# ControlModule-pan.net
KiCad netlist of a schematic drawn in EAGLE
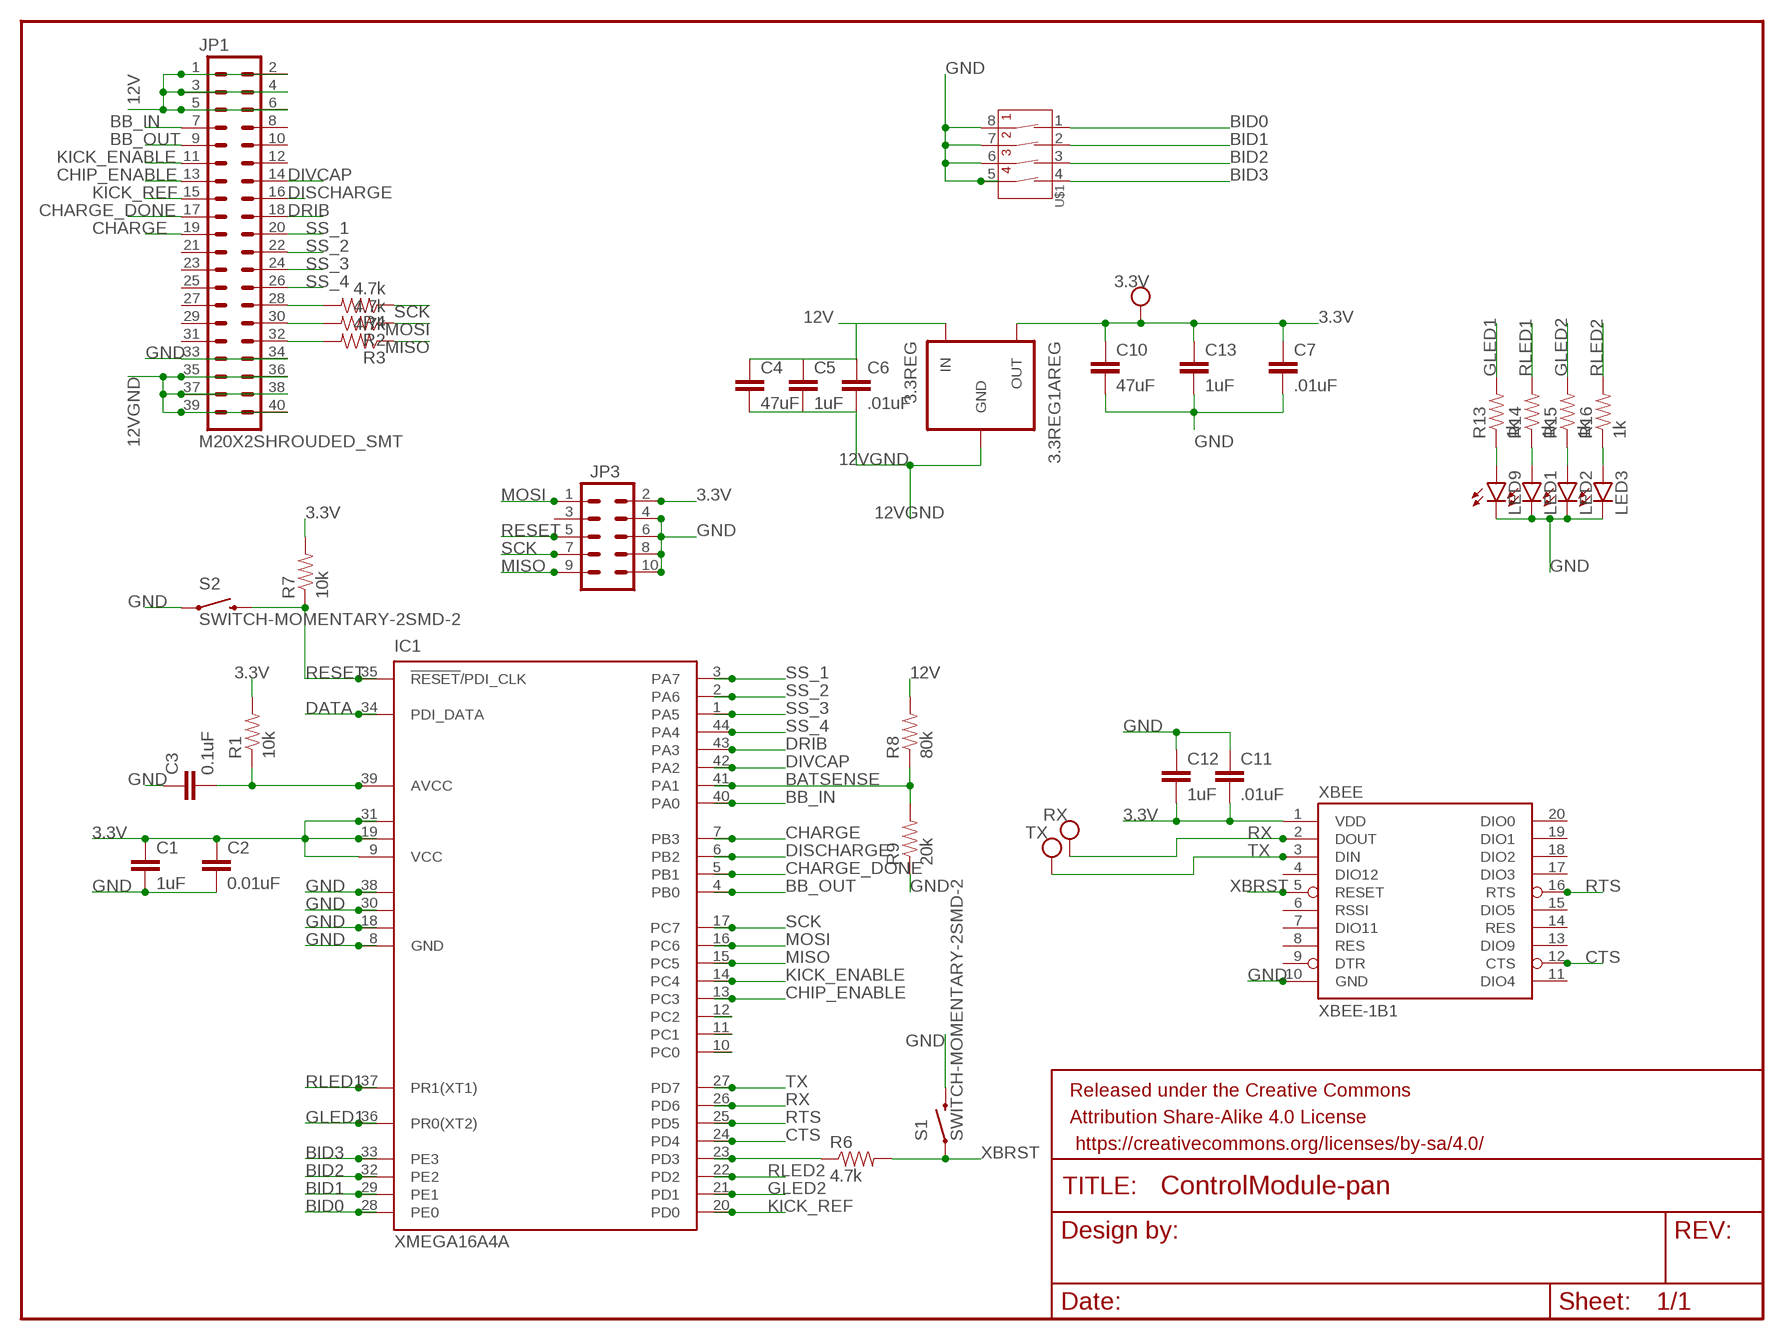
[diagram p0: schematic, sheet 1]

(export (version "E")
  (design (tool "Eeschema 10.0.6"))
  (components
    (comp (ref "3.3REG")
      (value "3.3REG1AREG")
      (footprint "eagle-import:DPAK")
      (libsource (lib "eagle-import") (part "3.3REG1AREG"))
    )
    (comp (ref "3.3V")
      (value "TEST_PT")
      (footprint "eagle-import:TESTING_PT")
      (libsource (lib "eagle-import") (part "TEST_PT"))
    )
    (comp (ref "C1")
      (value "1uF")
      (footprint "eagle-import:0805")
      (libsource (lib "eagle-import") (part "CAP0805"))
    )
    (comp (ref "C2")
      (value "0.01uF")
      (footprint "eagle-import:0805")
      (libsource (lib "eagle-import") (part "CAP0805"))
    )
    (comp (ref "C3")
      (value "0.1uF")
      (footprint "eagle-import:0805")
      (libsource (lib "eagle-import") (part "CAP0805"))
    )
    (comp (ref "C4")
      (value "47uF")
      (footprint "eagle-import:1206")
      (libsource (lib "eagle-import") (part "CAP1206"))
    )
    (comp (ref "C5")
      (value "1uF")
      (footprint "eagle-import:0805")
      (libsource (lib "eagle-import") (part "CAP0805"))
    )
    (comp (ref "C6")
      (value ".01uF")
      (footprint "eagle-import:0805")
      (libsource (lib "eagle-import") (part "CAP0805"))
    )
    (comp (ref "C7")
      (value ".01uF")
      (footprint "eagle-import:0805")
      (libsource (lib "eagle-import") (part "CAP0805"))
    )
    (comp (ref "C10")
      (value "47uF")
      (footprint "eagle-import:1206")
      (libsource (lib "eagle-import") (part "CAP1206"))
    )
    (comp (ref "C11")
      (value ".01uF")
      (footprint "eagle-import:0805")
      (libsource (lib "eagle-import") (part "CAP0805"))
    )
    (comp (ref "C12")
      (value "1uF")
      (footprint "eagle-import:0805")
      (libsource (lib "eagle-import") (part "CAP0805"))
    )
    (comp (ref "C13")
      (value "1uF")
      (footprint "eagle-import:0805")
      (libsource (lib "eagle-import") (part "CAP0805"))
    )
    (comp (ref "FRAME1")
      (value "FRAME-LETTER")
      (footprint "eagle-import:CREATIVE_COMMONS")
      (libsource (lib "eagle-import") (part "FRAME-LETTER"))
    )
    (comp (ref "IC1")
      (value "XMEGA16A4A")
      (footprint "eagle-import:TQFP44")
      (libsource (lib "eagle-import") (part "XMEGA16A4A"))
    )
    (comp (ref "JP1")
      (value "M20X2SHROUDED_SMT")
      (footprint "eagle-import:2X20_SHROUDED_SMT")
      (libsource (lib "eagle-import") (part "M20X2SHROUDED_SMT"))
    )
    (comp (ref "JP3")
      (value "M05X2SHD")
      (footprint "eagle-import:2X5-SHROUDED")
      (libsource (lib "eagle-import") (part "M05X2SHD"))
    )
    (comp (ref "LED1")
      (value "LED1206")
      (footprint "eagle-import:LED-1206")
      (libsource (lib "eagle-import") (part "LED1206"))
    )
    (comp (ref "LED2")
      (value "LED1206")
      (footprint "eagle-import:LED-1206")
      (libsource (lib "eagle-import") (part "LED1206"))
    )
    (comp (ref "LED3")
      (value "LED1206")
      (footprint "eagle-import:LED-1206")
      (libsource (lib "eagle-import") (part "LED1206"))
    )
    (comp (ref "LED9")
      (value "LED1206")
      (footprint "eagle-import:LED-1206")
      (libsource (lib "eagle-import") (part "LED1206"))
    )
    (comp (ref "R1")
      (value "10k")
      (footprint "eagle-import:0805")
      (libsource (lib "eagle-import") (part "RESISTOR0805-RES"))
    )
    (comp (ref "R2")
      (value "4.7k")
      (footprint "eagle-import:0805")
      (libsource (lib "eagle-import") (part "SparkFun-Resistors_RESISTOR0805-RES"))
    )
    (comp (ref "R3")
      (value "4.7k")
      (footprint "eagle-import:0805")
      (libsource (lib "eagle-import") (part "SparkFun-Resistors_RESISTOR0805-RES"))
    )
    (comp (ref "R4")
      (value "4.7k")
      (footprint "eagle-import:0805")
      (libsource (lib "eagle-import") (part "SparkFun-Resistors_RESISTOR0805-RES"))
    )
    (comp (ref "R6")
      (value "4.7k")
      (footprint "eagle-import:0805")
      (libsource (lib "eagle-import") (part "RESISTOR0805-RES"))
    )
    (comp (ref "R7")
      (value "10k")
      (footprint "eagle-import:0805")
      (libsource (lib "eagle-import") (part "RESISTOR0805-RES"))
    )
    (comp (ref "R8")
      (value "80k")
      (footprint "eagle-import:0805")
      (libsource (lib "eagle-import") (part "RESISTOR0805-RES"))
    )
    (comp (ref "R9")
      (value "20k")
      (footprint "eagle-import:0805")
      (libsource (lib "eagle-import") (part "RESISTOR0805-RES"))
    )
    (comp (ref "R13")
      (value "1k")
      (footprint "eagle-import:0805")
      (libsource (lib "eagle-import") (part "RESISTOR0805-RES"))
    )
    (comp (ref "R14")
      (value "1k")
      (footprint "eagle-import:0805")
      (libsource (lib "eagle-import") (part "RESISTOR0805-RES"))
    )
    (comp (ref "R15")
      (value "1k")
      (footprint "eagle-import:0805")
      (libsource (lib "eagle-import") (part "RESISTOR0805-RES"))
    )
    (comp (ref "R16")
      (value "1k")
      (footprint "eagle-import:0805")
      (libsource (lib "eagle-import") (part "RESISTOR0805-RES"))
    )
    (comp (ref "RX")
      (value "TEST_PT")
      (footprint "eagle-import:TESTING_PT")
      (libsource (lib "eagle-import") (part "TEST_PT"))
    )
    (comp (ref "S1")
      (value "SWITCH-MOMENTARY-2SMD-2")
      (footprint "eagle-import:TACTILE_SWITCH_SMD-2")
      (libsource (lib "eagle-import") (part "SWITCH-MOMENTARY-2SMD-2"))
    )
    (comp (ref "S2")
      (value "SWITCH-MOMENTARY-2SMD-2")
      (footprint "eagle-import:TACTILE_SWITCH_SMD-2")
      (libsource (lib "eagle-import") (part "SWITCH-MOMENTARY-2SMD-2"))
    )
    (comp (ref "TX")
      (value "TEST_PT")
      (footprint "eagle-import:TESTING_PT")
      (libsource (lib "eagle-import") (part "TEST_PT"))
    )
    (comp (ref "U$1")
      (value "4-POS-DIP")
      (footprint "eagle-import:4-POS-DIP-SMD")
      (libsource (lib "eagle-import") (part "4-POS-DIP"))
    )
    (comp (ref "XBEE")
      (value "XBEE-1B1")
      (footprint "eagle-import:XBEE-1")
      (libsource (lib "eagle-import") (part "XBEE-1B1"))
    )
  )
  (nets
    (net (code "1") (name "/3.3V") (class "Default")
      (node (ref "3.3REG") (pin "SOURCE") (pinfunction "OUT_SOURCE") (pintype "bidirectional"))
      (node (ref "3.3V") (pin "P$1") (pinfunction "P$1_P$1") (pintype "bidirectional"))
      (node (ref "C1") (pin "1") (pinfunction "1_1") (pintype "passive"))
      (node (ref "C10") (pin "1") (pinfunction "1_1") (pintype "passive"))
      (node (ref "C11") (pin "2") (pinfunction "2_2") (pintype "passive"))
      (node (ref "C12") (pin "2") (pinfunction "2_2") (pintype "passive"))
      (node (ref "C13") (pin "1") (pinfunction "1_1") (pintype "passive"))
      (node (ref "C2") (pin "1") (pinfunction "1_1") (pintype "passive"))
      (node (ref "C7") (pin "1") (pinfunction "1_1") (pintype "passive"))
      (node (ref "IC1") (pin "19") (pinfunction "VCC1_19") (pintype "power_in"))
      (node (ref "IC1") (pin "31") (pinfunction "VCC2_31") (pintype "power_in"))
      (node (ref "IC1") (pin "9") (pinfunction "VCC_9") (pintype "power_in"))
      (node (ref "JP3") (pin "2") (pinfunction "2_2") (pintype "passive"))
      (node (ref "R1") (pin "2") (pinfunction "2_2") (pintype "passive"))
      (node (ref "R7") (pin "2") (pinfunction "2_2") (pintype "passive"))
      (node (ref "XBEE") (pin "1") (pinfunction "VDD_1") (pintype "power_in"))
    )
    (net (code "2") (name "/12V") (class "Default")
      (node (ref "3.3REG") (pin "GATE") (pinfunction "IN_GATE") (pintype "input"))
      (node (ref "C4") (pin "1") (pinfunction "1_1") (pintype "passive"))
      (node (ref "C5") (pin "1") (pinfunction "1_1") (pintype "passive"))
      (node (ref "C6") (pin "1") (pinfunction "1_1") (pintype "passive"))
      (node (ref "JP1") (pin "1") (pinfunction "1_1") (pintype "passive"))
      (node (ref "JP1") (pin "2") (pinfunction "2_2") (pintype "passive"))
      (node (ref "JP1") (pin "3") (pinfunction "3_3") (pintype "passive"))
      (node (ref "JP1") (pin "4") (pinfunction "4_4") (pintype "passive"))
      (node (ref "JP1") (pin "5") (pinfunction "5_5") (pintype "passive"))
      (node (ref "JP1") (pin "6") (pinfunction "6_6") (pintype "passive"))
      (node (ref "R8") (pin "2") (pinfunction "2_2") (pintype "passive"))
    )
    (net (code "3") (name "/12VGND") (class "Default")
      (node (ref "3.3REG") (pin "DRAIN") (pinfunction "GND_DRAIN") (pintype "bidirectional"))
      (node (ref "C4") (pin "2") (pinfunction "2_2") (pintype "passive"))
      (node (ref "C5") (pin "2") (pinfunction "2_2") (pintype "passive"))
      (node (ref "C6") (pin "2") (pinfunction "2_2") (pintype "passive"))
      (node (ref "JP1") (pin "35") (pinfunction "35_35") (pintype "passive"))
      (node (ref "JP1") (pin "36") (pinfunction "36_36") (pintype "passive"))
      (node (ref "JP1") (pin "37") (pinfunction "37_37") (pintype "passive"))
      (node (ref "JP1") (pin "38") (pinfunction "38_38") (pintype "passive"))
      (node (ref "JP1") (pin "39") (pinfunction "39_39") (pintype "passive"))
      (node (ref "JP1") (pin "40") (pinfunction "40_40") (pintype "passive"))
    )
    (net (code "4") (name "/BATSENSE") (class "Default")
      (node (ref "IC1") (pin "41") (pinfunction "PA1_41") (pintype "bidirectional"))
      (node (ref "R8") (pin "1") (pinfunction "1_1") (pintype "passive"))
      (node (ref "R9") (pin "2") (pinfunction "2_2") (pintype "passive"))
    )
    (net (code "5") (name "/BB_IN") (class "Default")
      (node (ref "IC1") (pin "40") (pinfunction "PA0_40") (pintype "bidirectional"))
      (node (ref "JP1") (pin "7") (pinfunction "7_7") (pintype "passive"))
    )
    (net (code "6") (name "/BB_OUT") (class "Default")
      (node (ref "IC1") (pin "4") (pinfunction "PB0_4") (pintype "bidirectional"))
      (node (ref "JP1") (pin "9") (pinfunction "9_9") (pintype "passive"))
    )
    (net (code "7") (name "/BID0") (class "Default")
      (node (ref "IC1") (pin "28") (pinfunction "PE0_28") (pintype "bidirectional"))
      (node (ref "U$1") (pin "1") (pinfunction "1A_1") (pintype "bidirectional"))
    )
    (net (code "8") (name "/BID1") (class "Default")
      (node (ref "IC1") (pin "29") (pinfunction "PE1_29") (pintype "bidirectional"))
      (node (ref "U$1") (pin "2") (pinfunction "2A_2") (pintype "bidirectional"))
    )
    (net (code "9") (name "/BID2") (class "Default")
      (node (ref "IC1") (pin "32") (pinfunction "PE2_32") (pintype "bidirectional"))
      (node (ref "U$1") (pin "3") (pinfunction "3A_3") (pintype "bidirectional"))
    )
    (net (code "10") (name "/BID3") (class "Default")
      (node (ref "IC1") (pin "33") (pinfunction "PE3_33") (pintype "bidirectional"))
      (node (ref "U$1") (pin "4") (pinfunction "4A_4") (pintype "bidirectional"))
    )
    (net (code "11") (name "/CHARGE") (class "Default")
      (node (ref "IC1") (pin "7") (pinfunction "PB3_7") (pintype "bidirectional"))
      (node (ref "JP1") (pin "19") (pinfunction "19_19") (pintype "passive"))
    )
    (net (code "12") (name "/CHARGE_DONE") (class "Default")
      (node (ref "IC1") (pin "5") (pinfunction "PB1_5") (pintype "bidirectional"))
      (node (ref "JP1") (pin "17") (pinfunction "17_17") (pintype "passive"))
    )
    (net (code "13") (name "/CHIP_ENABLE") (class "Default")
      (node (ref "IC1") (pin "13") (pinfunction "PC3_13") (pintype "bidirectional"))
      (node (ref "JP1") (pin "13") (pinfunction "13_13") (pintype "passive"))
    )
    (net (code "14") (name "/CTS") (class "Default")
      (node (ref "IC1") (pin "24") (pinfunction "PD4_24") (pintype "bidirectional"))
      (node (ref "XBEE") (pin "12") (pinfunction "CTS_12") (pintype "output"))
    )
    (net (code "15") (name "/DATA") (class "Default")
      (node (ref "IC1") (pin "34") (pinfunction "PDI_DATA_34") (pintype "bidirectional"))
    )
    (net (code "16") (name "/DISCHARGE") (class "Default")
      (node (ref "IC1") (pin "6") (pinfunction "PB2_6") (pintype "bidirectional"))
      (node (ref "JP1") (pin "16") (pinfunction "16_16") (pintype "passive"))
    )
    (net (code "17") (name "/DIVCAP") (class "Default")
      (node (ref "IC1") (pin "42") (pinfunction "PA2_42") (pintype "bidirectional"))
      (node (ref "JP1") (pin "14") (pinfunction "14_14") (pintype "passive"))
    )
    (net (code "18") (name "/DRIB") (class "Default")
      (node (ref "IC1") (pin "43") (pinfunction "PA3_43") (pintype "bidirectional"))
      (node (ref "JP1") (pin "18") (pinfunction "18_18") (pintype "passive"))
    )
    (net (code "19") (name "/GLED1") (class "Default")
      (node (ref "IC1") (pin "36") (pinfunction "PR0(XT2)_36") (pintype "bidirectional"))
      (node (ref "R13") (pin "2") (pinfunction "2_2") (pintype "passive"))
    )
    (net (code "20") (name "/GLED2") (class "Default")
      (node (ref "IC1") (pin "21") (pinfunction "PD1_21") (pintype "bidirectional"))
      (node (ref "R15") (pin "2") (pinfunction "2_2") (pintype "passive"))
    )
    (net (code "21") (name "/GND") (class "Default")
      (node (ref "C1") (pin "2") (pinfunction "2_2") (pintype "passive"))
      (node (ref "C10") (pin "2") (pinfunction "2_2") (pintype "passive"))
      (node (ref "C11") (pin "1") (pinfunction "1_1") (pintype "passive"))
      (node (ref "C12") (pin "1") (pinfunction "1_1") (pintype "passive"))
      (node (ref "C13") (pin "2") (pinfunction "2_2") (pintype "passive"))
      (node (ref "C2") (pin "2") (pinfunction "2_2") (pintype "passive"))
      (node (ref "C3") (pin "1") (pinfunction "1_1") (pintype "passive"))
      (node (ref "C7") (pin "2") (pinfunction "2_2") (pintype "passive"))
      (node (ref "IC1") (pin "18") (pinfunction "GND1_18") (pintype "power_in"))
      (node (ref "IC1") (pin "30") (pinfunction "GND2_30") (pintype "power_in"))
      (node (ref "IC1") (pin "38") (pinfunction "GND3_38") (pintype "power_in"))
      (node (ref "IC1") (pin "8") (pinfunction "GND_8") (pintype "power_in"))
      (node (ref "JP1") (pin "33") (pinfunction "33_33") (pintype "passive"))
      (node (ref "JP1") (pin "34") (pinfunction "34_34") (pintype "passive"))
      (node (ref "JP3") (pin "10") (pinfunction "10_10") (pintype "passive"))
      (node (ref "JP3") (pin "4") (pinfunction "4_4") (pintype "passive"))
      (node (ref "JP3") (pin "6") (pinfunction "6_6") (pintype "passive"))
      (node (ref "JP3") (pin "8") (pinfunction "8_8") (pintype "passive"))
      (node (ref "LED1") (pin "C") (pinfunction "C_C") (pintype "passive"))
      (node (ref "LED2") (pin "C") (pinfunction "C_C") (pintype "passive"))
      (node (ref "LED3") (pin "C") (pinfunction "C_C") (pintype "passive"))
      (node (ref "LED9") (pin "C") (pinfunction "C_C") (pintype "passive"))
      (node (ref "R9") (pin "1") (pinfunction "1_1") (pintype "passive"))
      (node (ref "S1") (pin "1") (pinfunction "2_1") (pintype "passive"))
      (node (ref "S2") (pin "2") (pinfunction "1_2") (pintype "passive"))
      (node (ref "U$1") (pin "5") (pinfunction "4B_5") (pintype "bidirectional"))
      (node (ref "U$1") (pin "6") (pinfunction "3B_6") (pintype "bidirectional"))
      (node (ref "U$1") (pin "7") (pinfunction "2B_7") (pintype "bidirectional"))
      (node (ref "U$1") (pin "8") (pinfunction "1B_8") (pintype "bidirectional"))
      (node (ref "XBEE") (pin "10") (pinfunction "GND_10") (pintype "power_in"))
    )
    (net (code "22") (name "/KICK_ENABLE") (class "Default")
      (node (ref "IC1") (pin "14") (pinfunction "PC4_14") (pintype "bidirectional"))
      (node (ref "JP1") (pin "11") (pinfunction "11_11") (pintype "passive"))
    )
    (net (code "23") (name "/KICK_REF") (class "Default")
      (node (ref "IC1") (pin "20") (pinfunction "PD0_20") (pintype "bidirectional"))
      (node (ref "JP1") (pin "15") (pinfunction "15_15") (pintype "passive"))
    )
    (net (code "24") (name "/MISO") (class "Default")
      (node (ref "IC1") (pin "15") (pinfunction "PC5_15") (pintype "bidirectional"))
      (node (ref "JP3") (pin "9") (pinfunction "9_9") (pintype "passive"))
      (node (ref "R3") (pin "1") (pinfunction "1_1") (pintype "passive"))
    )
    (net (code "25") (name "/MOSI") (class "Default")
      (node (ref "IC1") (pin "16") (pinfunction "PC6_16") (pintype "bidirectional"))
      (node (ref "JP3") (pin "1") (pinfunction "1_1") (pintype "passive"))
      (node (ref "R2") (pin "1") (pinfunction "1_1") (pintype "passive"))
    )
    (net (code "26") (name "/RESET") (class "Default")
      (node (ref "IC1") (pin "35") (pinfunction "~{RESET}/PDI_CLK_35") (pintype "bidirectional"))
      (node (ref "JP3") (pin "5") (pinfunction "5_5") (pintype "passive"))
      (node (ref "R7") (pin "1") (pinfunction "1_1") (pintype "passive"))
      (node (ref "S2") (pin "1") (pinfunction "2_1") (pintype "passive"))
    )
    (net (code "27") (name "/RLED1") (class "Default")
      (node (ref "IC1") (pin "37") (pinfunction "PR1(XT1)_37") (pintype "bidirectional"))
      (node (ref "R14") (pin "2") (pinfunction "2_2") (pintype "passive"))
    )
    (net (code "28") (name "/RLED2") (class "Default")
      (node (ref "IC1") (pin "22") (pinfunction "PD2_22") (pintype "bidirectional"))
      (node (ref "R16") (pin "2") (pinfunction "2_2") (pintype "passive"))
    )
    (net (code "29") (name "/RTS") (class "Default")
      (node (ref "IC1") (pin "25") (pinfunction "PD5_25") (pintype "bidirectional"))
      (node (ref "XBEE") (pin "16") (pinfunction "RTS_16") (pintype "input"))
    )
    (net (code "30") (name "/RX") (class "Default")
      (node (ref "IC1") (pin "26") (pinfunction "PD6_26") (pintype "bidirectional"))
      (node (ref "RX") (pin "P$1") (pinfunction "P$1_P$1") (pintype "bidirectional"))
      (node (ref "XBEE") (pin "2") (pinfunction "DOUT_2") (pintype "output"))
    )
    (net (code "31") (name "/SCK") (class "Default")
      (node (ref "IC1") (pin "17") (pinfunction "PC7_17") (pintype "bidirectional"))
      (node (ref "JP3") (pin "7") (pinfunction "7_7") (pintype "passive"))
      (node (ref "R4") (pin "1") (pinfunction "1_1") (pintype "passive"))
    )
    (net (code "32") (name "/SS_1") (class "Default")
      (node (ref "IC1") (pin "3") (pinfunction "PA7_3") (pintype "bidirectional"))
      (node (ref "JP1") (pin "20") (pinfunction "20_20") (pintype "passive"))
    )
    (net (code "33") (name "/SS_2") (class "Default")
      (node (ref "IC1") (pin "2") (pinfunction "PA6_2") (pintype "bidirectional"))
      (node (ref "JP1") (pin "22") (pinfunction "22_22") (pintype "passive"))
    )
    (net (code "34") (name "/SS_3") (class "Default")
      (node (ref "IC1") (pin "1") (pinfunction "PA5_1") (pintype "bidirectional"))
      (node (ref "JP1") (pin "24") (pinfunction "24_24") (pintype "passive"))
    )
    (net (code "35") (name "/SS_4") (class "Default")
      (node (ref "IC1") (pin "44") (pinfunction "PA4_44") (pintype "bidirectional"))
      (node (ref "JP1") (pin "26") (pinfunction "26_26") (pintype "passive"))
    )
    (net (code "36") (name "/TX") (class "Default")
      (node (ref "IC1") (pin "27") (pinfunction "PD7_27") (pintype "bidirectional"))
      (node (ref "TX") (pin "P$1") (pinfunction "P$1_P$1") (pintype "bidirectional"))
      (node (ref "XBEE") (pin "3") (pinfunction "DIN_3") (pintype "input"))
    )
    (net (code "37") (name "/XBRST") (class "Default")
      (node (ref "R6") (pin "2") (pinfunction "2_2") (pintype "passive"))
      (node (ref "S1") (pin "2") (pinfunction "1_2") (pintype "passive"))
      (node (ref "XBEE") (pin "5") (pinfunction "RESET_5") (pintype "input"))
    )
    (net (code "38") (name "Net-(IC1-AVCC)") (class "Default")
      (node (ref "C3") (pin "2") (pinfunction "2_2") (pintype "passive"))
      (node (ref "IC1") (pin "39") (pinfunction "AVCC_39") (pintype "power_in"))
      (node (ref "R1") (pin "1") (pinfunction "1_1") (pintype "passive"))
    )
    (net (code "39") (name "Net-(IC1-PD3)") (class "Default")
      (node (ref "IC1") (pin "23") (pinfunction "PD3_23") (pintype "bidirectional"))
      (node (ref "R6") (pin "1") (pinfunction "1_1") (pintype "passive"))
    )
    (net (code "40") (name "Net-(JP1-Pad28)") (class "Default")
      (node (ref "JP1") (pin "28") (pinfunction "28_28") (pintype "passive"))
      (node (ref "R4") (pin "2") (pinfunction "2_2") (pintype "passive"))
    )
    (net (code "41") (name "Net-(JP1-Pad30)") (class "Default")
      (node (ref "JP1") (pin "30") (pinfunction "30_30") (pintype "passive"))
      (node (ref "R2") (pin "2") (pinfunction "2_2") (pintype "passive"))
    )
    (net (code "42") (name "Net-(JP1-Pad32)") (class "Default")
      (node (ref "JP1") (pin "32") (pinfunction "32_32") (pintype "passive"))
      (node (ref "R3") (pin "2") (pinfunction "2_2") (pintype "passive"))
    )
    (net (code "43") (name "Net-(LED1-PadA)") (class "Default")
      (node (ref "LED1") (pin "A") (pinfunction "A_A") (pintype "passive"))
      (node (ref "R14") (pin "1") (pinfunction "1_1") (pintype "passive"))
    )
    (net (code "44") (name "Net-(LED2-PadA)") (class "Default")
      (node (ref "LED2") (pin "A") (pinfunction "A_A") (pintype "passive"))
      (node (ref "R15") (pin "1") (pinfunction "1_1") (pintype "passive"))
    )
    (net (code "45") (name "Net-(LED3-PadA)") (class "Default")
      (node (ref "LED3") (pin "A") (pinfunction "A_A") (pintype "passive"))
      (node (ref "R16") (pin "1") (pinfunction "1_1") (pintype "passive"))
    )
    (net (code "46") (name "Net-(LED9-PadA)") (class "Default")
      (node (ref "LED9") (pin "A") (pinfunction "A_A") (pintype "passive"))
      (node (ref "R13") (pin "1") (pinfunction "1_1") (pintype "passive"))
    )
    (net (code "47") (name "unconnected-(IC1-PC0-Pad10)") (class "Default")
      (node (ref "IC1") (pin "10") (pinfunction "PC0_10") (pintype "bidirectional"))
    )
    (net (code "48") (name "unconnected-(IC1-PC1-Pad11)") (class "Default")
      (node (ref "IC1") (pin "11") (pinfunction "PC1_11") (pintype "bidirectional"))
    )
    (net (code "49") (name "unconnected-(IC1-PC2-Pad12)") (class "Default")
      (node (ref "IC1") (pin "12") (pinfunction "PC2_12") (pintype "bidirectional"))
    )
    (net (code "50") (name "unconnected-(JP1-Pad8)") (class "Default")
      (node (ref "JP1") (pin "8") (pinfunction "8_8") (pintype "passive"))
    )
    (net (code "51") (name "unconnected-(JP1-Pad10)") (class "Default")
      (node (ref "JP1") (pin "10") (pinfunction "10_10") (pintype "passive"))
    )
    (net (code "52") (name "unconnected-(JP1-Pad12)") (class "Default")
      (node (ref "JP1") (pin "12") (pinfunction "12_12") (pintype "passive"))
    )
    (net (code "53") (name "unconnected-(JP1-Pad21)") (class "Default")
      (node (ref "JP1") (pin "21") (pinfunction "21_21") (pintype "passive"))
    )
    (net (code "54") (name "unconnected-(JP1-Pad23)") (class "Default")
      (node (ref "JP1") (pin "23") (pinfunction "23_23") (pintype "passive"))
    )
    (net (code "55") (name "unconnected-(JP1-Pad25)") (class "Default")
      (node (ref "JP1") (pin "25") (pinfunction "25_25") (pintype "passive"))
    )
    (net (code "56") (name "unconnected-(JP1-Pad27)") (class "Default")
      (node (ref "JP1") (pin "27") (pinfunction "27_27") (pintype "passive"))
    )
    (net (code "57") (name "unconnected-(JP1-Pad29)") (class "Default")
      (node (ref "JP1") (pin "29") (pinfunction "29_29") (pintype "passive"))
    )
    (net (code "58") (name "unconnected-(JP1-Pad31)") (class "Default")
      (node (ref "JP1") (pin "31") (pinfunction "31_31") (pintype "passive"))
    )
    (net (code "59") (name "unconnected-(JP3-Pad3)") (class "Default")
      (node (ref "JP3") (pin "3") (pinfunction "3_3") (pintype "passive"))
    )
    (net (code "60") (name "unconnected-(XBEE-DIO0-Pad20)") (class "Default")
      (node (ref "XBEE") (pin "20") (pinfunction "DIO0_20") (pintype "bidirectional"))
    )
    (net (code "61") (name "unconnected-(XBEE-DIO1-Pad19)") (class "Default")
      (node (ref "XBEE") (pin "19") (pinfunction "DIO1_19") (pintype "bidirectional"))
    )
    (net (code "62") (name "unconnected-(XBEE-DIO2-Pad18)") (class "Default")
      (node (ref "XBEE") (pin "18") (pinfunction "DIO2_18") (pintype "bidirectional"))
    )
    (net (code "63") (name "unconnected-(XBEE-DIO3-Pad17)") (class "Default")
      (node (ref "XBEE") (pin "17") (pinfunction "DIO3_17") (pintype "bidirectional"))
    )
    (net (code "64") (name "unconnected-(XBEE-DIO4-Pad11)") (class "Default")
      (node (ref "XBEE") (pin "11") (pinfunction "DIO4_11") (pintype "bidirectional"))
    )
    (net (code "65") (name "unconnected-(XBEE-DIO5-Pad15)") (class "Default")
      (node (ref "XBEE") (pin "15") (pinfunction "DIO5_15") (pintype "bidirectional"))
    )
    (net (code "66") (name "unconnected-(XBEE-DIO9-Pad13)") (class "Default")
      (node (ref "XBEE") (pin "13") (pinfunction "DIO9_13") (pintype "bidirectional"))
    )
    (net (code "67") (name "unconnected-(XBEE-DIO11-Pad7)") (class "Default")
      (node (ref "XBEE") (pin "7") (pinfunction "DIO11_7") (pintype "bidirectional"))
    )
    (net (code "68") (name "unconnected-(XBEE-DIO12-Pad4)") (class "Default")
      (node (ref "XBEE") (pin "4") (pinfunction "DIO12_4") (pintype "bidirectional"))
    )
    (net (code "69") (name "unconnected-(XBEE-DTR-Pad9)") (class "Default")
      (node (ref "XBEE") (pin "9") (pinfunction "DTR_9") (pintype "bidirectional"))
    )
    (net (code "70") (name "unconnected-(XBEE-RES-Pad8)") (class "Default")
      (node (ref "XBEE") (pin "8") (pinfunction "RES_8") (pintype "bidirectional"))
    )
    (net (code "71") (name "unconnected-(XBEE-RES-Pad14)") (class "Default")
      (node (ref "XBEE") (pin "14") (pinfunction "RES_14") (pintype "bidirectional"))
    )
    (net (code "72") (name "unconnected-(XBEE-RSSI-Pad6)") (class "Default")
      (node (ref "XBEE") (pin "6") (pinfunction "RSSI_6") (pintype "bidirectional"))
    )
  )
)
